# design.net
KiCad netlist of a schematic drawn in Altium Designer
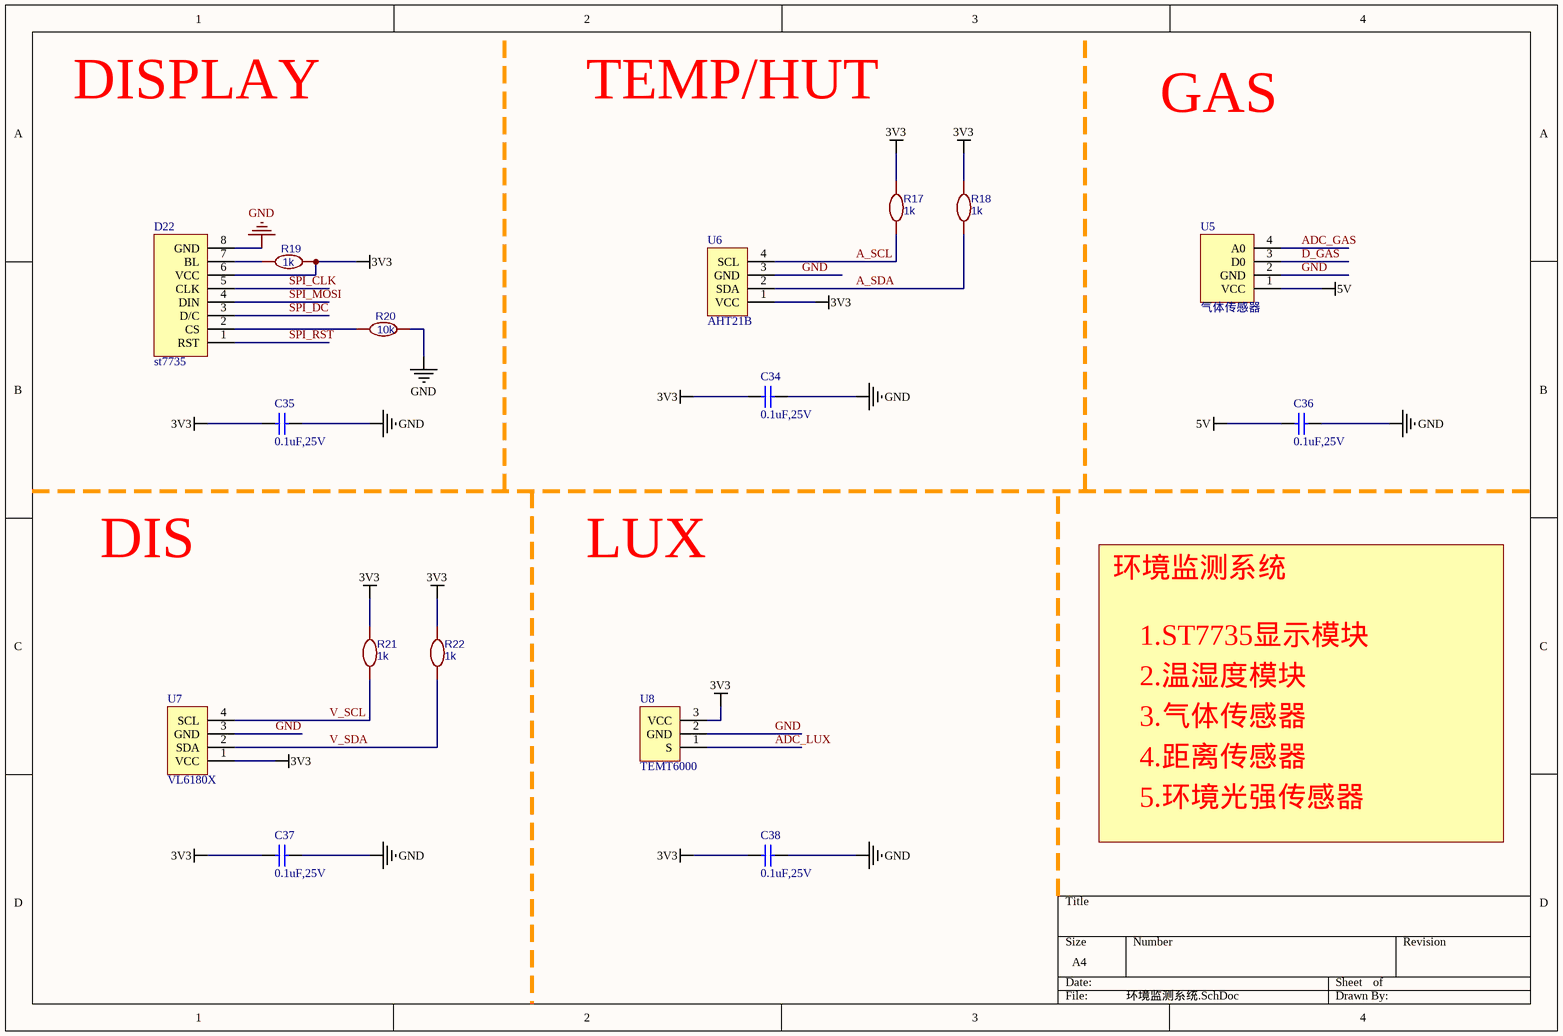
[diagram p0: 环境监测系统.SchDoc]

(export (version "E")
  (design (tool "Eeschema 10.0.6"))
  (components
    (comp (ref "C34")
      (value "0.1uF,25V")
      (footprint "0402_C")
      (description "贴片电容")
      (fields (field (name "PART NUMBER") "T_Cap_0603_0.1uF_25V_X5R") (field (name "TOLERANCE") "10%"))
      (libsource (lib "Database_Library") (part "Cap"))
    )
    (comp (ref "C35")
      (value "0.1uF,25V")
      (footprint "0402_C")
      (description "贴片电容")
      (fields (field (name "PART NUMBER") "T_Cap_0603_0.1uF_25V_X5R") (field (name "TOLERANCE") "10%"))
      (libsource (lib "Database_Library") (part "Cap"))
    )
    (comp (ref "C36")
      (value "0.1uF,25V")
      (footprint "0402_C")
      (description "贴片电容")
      (fields (field (name "PART NUMBER") "T_Cap_0603_0.1uF_25V_X5R") (field (name "TOLERANCE") "10%"))
      (libsource (lib "Database_Library") (part "Cap"))
    )
    (comp (ref "C37")
      (value "0.1uF,25V")
      (footprint "0402_C")
      (description "贴片电容")
      (fields (field (name "PART NUMBER") "T_Cap_0603_0.1uF_25V_X5R") (field (name "TOLERANCE") "10%"))
      (libsource (lib "Database_Library") (part "Cap"))
    )
    (comp (ref "C38")
      (value "0.1uF,25V")
      (footprint "0402_C")
      (description "贴片电容")
      (fields (field (name "PART NUMBER") "T_Cap_0603_0.1uF_25V_X5R") (field (name "TOLERANCE") "10%"))
      (libsource (lib "Database_Library") (part "Cap"))
    )
    (comp (ref "D22") (value "st7735") (footprint "HDR1X8") (libsource (lib "Schlib_PICO") (part "st7735")))
    (comp (ref "R17")
      (value "1k")
      (footprint "0402_R")
      (fields (field (name "CONTRIBUTOR") "LCEDA_Lib"))
      (libsource (lib "altium-import") (part "root_1_1k_"))
    )
    (comp (ref "R18")
      (value "1k")
      (footprint "0402_R")
      (fields (field (name "CONTRIBUTOR") "LCEDA_Lib"))
      (libsource (lib "altium-import") (part "root_1_1k_"))
    )
    (comp (ref "R19")
      (value "1k")
      (footprint "0402_R")
      (fields (field (name "CONTRIBUTOR") "LCEDA_Lib"))
      (libsource (lib "altium-import") (part "root_0_1k_"))
    )
    (comp (ref "R20")
      (value "10k")
      (footprint "0402_R")
      (fields (field (name "CONTRIBUTOR") "LCEDA_Lib"))
      (libsource (lib "altium-import") (part "root_0_1k_"))
    )
    (comp (ref "R21")
      (value "1k")
      (footprint "0402_R")
      (fields (field (name "CONTRIBUTOR") "LCEDA_Lib"))
      (libsource (lib "altium-import") (part "root_1_1k_"))
    )
    (comp (ref "R22")
      (value "1k")
      (footprint "0402_R")
      (fields (field (name "CONTRIBUTOR") "LCEDA_Lib"))
      (libsource (lib "altium-import") (part "root_1_1k_"))
    )
    (comp (ref "U5") (value "气体传感器") (footprint "XH2.54A-4") (libsource (lib "Schlib_PICO") (part "MQ135")))
    (comp (ref "U6") (value "AHT21B") (footprint "XH2.54A-4") (libsource (lib "Schlib_PICO") (part "AHT21B")))
    (comp (ref "U7")
      (value "VL6180X")
      (footprint "XH2.54A-4")
      (libsource (lib "Schlib_PICO") (part "VL6180X"))
    )
    (comp (ref "U8")
      (value "TEMT6000")
      (footprint "XH2.54A-3")
      (libsource (lib "Schlib_PICO") (part "TEMT6000"))
    )
  )
  (nets
    (net (code "1") (name "/ADC_GAS") (class "Default")
      (node (ref "U5") (pin "4") (pinfunction "A0_4") (pintype "passive"))
    )
    (net (code "2") (name "/ADC_LUX") (class "Default")
      (node (ref "U8") (pin "1") (pinfunction "S_1") (pintype "passive"))
    )
    (net (code "3") (name "/A_SCL") (class "Default")
      (node (ref "R17") (pin "1") (pinfunction "1_1") (pintype "passive"))
      (node (ref "U6") (pin "4") (pinfunction "SCL_4") (pintype "passive"))
    )
    (net (code "4") (name "/A_SDA") (class "Default")
      (node (ref "R18") (pin "1") (pinfunction "1_1") (pintype "passive"))
      (node (ref "U6") (pin "2") (pinfunction "SDA_2") (pintype "passive"))
    )
    (net (code "5") (name "/D_GAS") (class "Default")
      (node (ref "U5") (pin "3") (pinfunction "D0_3") (pintype "passive"))
    )
    (net (code "6") (name "/SPI_CLK") (class "Default")
      (node (ref "D22") (pin "5") (pinfunction "CLK_5") (pintype "passive"))
    )
    (net (code "7") (name "/SPI_DC") (class "Default")
      (node (ref "D22") (pin "3") (pinfunction "D/C_3") (pintype "passive"))
    )
    (net (code "8") (name "/SPI_MOSI") (class "Default")
      (node (ref "D22") (pin "4") (pinfunction "DIN_4") (pintype "passive"))
    )
    (net (code "9") (name "/SPI_RST") (class "Default")
      (node (ref "D22") (pin "1") (pinfunction "RST_1") (pintype "passive"))
    )
    (net (code "10") (name "/V_SCL") (class "Default")
      (node (ref "R21") (pin "1") (pinfunction "1_1") (pintype "passive"))
      (node (ref "U7") (pin "4") (pinfunction "SCL_4") (pintype "passive"))
    )
    (net (code "11") (name "/V_SDA") (class "Default")
      (node (ref "R22") (pin "1") (pinfunction "1_1") (pintype "passive"))
      (node (ref "U7") (pin "2") (pinfunction "SDA_2") (pintype "passive"))
    )
    (net (code "12") (name "3V3") (class "Default")
      (node (ref "C34") (pin "2") (pinfunction "2_2") (pintype "passive"))
      (node (ref "C35") (pin "2") (pinfunction "2_2") (pintype "passive"))
      (node (ref "C37") (pin "2") (pinfunction "2_2") (pintype "passive"))
      (node (ref "C38") (pin "2") (pinfunction "2_2") (pintype "passive"))
      (node (ref "D22") (pin "6") (pinfunction "VCC_6") (pintype "passive"))
      (node (ref "R17") (pin "2") (pinfunction "2_2") (pintype "passive"))
      (node (ref "R18") (pin "2") (pinfunction "2_2") (pintype "passive"))
      (node (ref "R19") (pin "2") (pinfunction "2_2") (pintype "passive"))
      (node (ref "R21") (pin "2") (pinfunction "2_2") (pintype "passive"))
      (node (ref "R22") (pin "2") (pinfunction "2_2") (pintype "passive"))
      (node (ref "U6") (pin "1") (pinfunction "VCC_1") (pintype "passive"))
      (node (ref "U7") (pin "1") (pinfunction "VCC_1") (pintype "passive"))
      (node (ref "U8") (pin "3") (pinfunction "VCC_3") (pintype "passive"))
    )
    (net (code "13") (name "5V") (class "Default")
      (node (ref "C36") (pin "2") (pinfunction "2_2") (pintype "passive"))
      (node (ref "U5") (pin "1") (pinfunction "VCC_1") (pintype "passive"))
    )
    (net (code "14") (name "GND") (class "Default")
      (node (ref "C34") (pin "1") (pinfunction "1_1") (pintype "passive"))
      (node (ref "C35") (pin "1") (pinfunction "1_1") (pintype "passive"))
      (node (ref "C36") (pin "1") (pinfunction "1_1") (pintype "passive"))
      (node (ref "C37") (pin "1") (pinfunction "1_1") (pintype "passive"))
      (node (ref "C38") (pin "1") (pinfunction "1_1") (pintype "passive"))
      (node (ref "D22") (pin "8") (pinfunction "GND_8") (pintype "passive"))
      (node (ref "R20") (pin "2") (pinfunction "2_2") (pintype "passive"))
      (node (ref "U5") (pin "2") (pinfunction "GND_2") (pintype "passive"))
      (node (ref "U6") (pin "3") (pinfunction "GND_3") (pintype "passive"))
      (node (ref "U7") (pin "3") (pinfunction "GND_3") (pintype "passive"))
      (node (ref "U8") (pin "2") (pinfunction "GND_2") (pintype "passive"))
    )
    (net (code "15") (name "Net-(D22-BL)") (class "Default")
      (node (ref "D22") (pin "7") (pinfunction "BL_7") (pintype "passive"))
      (node (ref "R19") (pin "1") (pinfunction "1_1") (pintype "passive"))
    )
    (net (code "16") (name "Net-(D22-CS)") (class "Default")
      (node (ref "D22") (pin "2") (pinfunction "CS_2") (pintype "passive"))
      (node (ref "R20") (pin "1") (pinfunction "1_1") (pintype "passive"))
    )
  )
)
